# ardu_uno_car.net
KiCad netlist of a schematic drawn in EAGLE
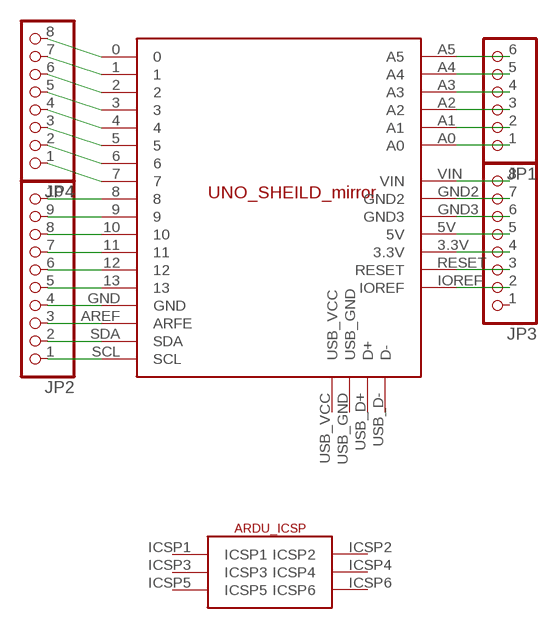
[diagram p0: schematic, sheet 1]

(export (version "E")
  (design (tool "Eeschema 10.0.6"))
  (components
    (comp (ref "JP1")
      (value "PINHEAD_PINHD-1X6")
      (footprint "eagle-import:PINHEAD_1X06")
      (libsource (lib "eagle-import") (part "PINHEAD_PINHD-1X6"))
    )
    (comp (ref "JP2")
      (value "PINHD-1X10")
      (footprint "eagle-import:1X10")
      (libsource (lib "eagle-import") (part "PINHD-1X10"))
    )
    (comp (ref "JP3")
      (value "PINHEAD_PINHD-1X8")
      (footprint "eagle-import:PINHEAD_1X08")
      (libsource (lib "eagle-import") (part "PINHEAD_PINHD-1X8"))
    )
    (comp (ref "JP4")
      (value "PINHEAD_PINHD-1X8")
      (footprint "eagle-import:PINHEAD_1X08")
      (libsource (lib "eagle-import") (part "PINHEAD_PINHD-1X8"))
    )
    (comp (ref "U$1")
      (value "UNO_SHEILD_MIRROR_CH_VER")
      (footprint "eagle-import:UNO_SHEILD_MIRROR_CH_VER")
      (libsource (lib "eagle-import") (part "UNO_SHEILD_MIRROR_CH_VER"))
    )
  )
  (nets
    (net (code "1") (name "Net-(JP1-Pad1)") (class "Default")
      (node (ref "JP1") (pin "1") (pinfunction "1_1") (pintype "passive"))
      (node (ref "U$1") (pin "A0") (pinfunction "A0_A0") (pintype "bidirectional"))
    )
    (net (code "2") (name "Net-(JP1-Pad2)") (class "Default")
      (node (ref "JP1") (pin "2") (pinfunction "2_2") (pintype "passive"))
      (node (ref "U$1") (pin "A1") (pinfunction "A1_A1") (pintype "bidirectional"))
    )
    (net (code "3") (name "Net-(JP1-Pad3)") (class "Default")
      (node (ref "JP1") (pin "3") (pinfunction "3_3") (pintype "passive"))
      (node (ref "U$1") (pin "A2") (pinfunction "A2_A2") (pintype "bidirectional"))
    )
    (net (code "4") (name "Net-(JP1-Pad4)") (class "Default")
      (node (ref "JP1") (pin "4") (pinfunction "4_4") (pintype "passive"))
      (node (ref "U$1") (pin "A3") (pinfunction "A3_A3") (pintype "bidirectional"))
    )
    (net (code "5") (name "Net-(JP1-Pad5)") (class "Default")
      (node (ref "JP1") (pin "5") (pinfunction "5_5") (pintype "passive"))
      (node (ref "U$1") (pin "A4") (pinfunction "A4_A4") (pintype "bidirectional"))
    )
    (net (code "6") (name "Net-(JP1-Pad6)") (class "Default")
      (node (ref "JP1") (pin "6") (pinfunction "6_6") (pintype "passive"))
      (node (ref "U$1") (pin "A5") (pinfunction "A5_A5") (pintype "bidirectional"))
    )
    (net (code "7") (name "Net-(JP2-Pad1)") (class "Default")
      (node (ref "JP2") (pin "1") (pinfunction "1_1") (pintype "passive"))
      (node (ref "U$1") (pin "SCL") (pinfunction "SCL_SCL") (pintype "bidirectional"))
    )
    (net (code "8") (name "Net-(JP2-Pad2)") (class "Default")
      (node (ref "JP2") (pin "2") (pinfunction "2_2") (pintype "passive"))
      (node (ref "U$1") (pin "SDA") (pinfunction "SDA_SDA") (pintype "bidirectional"))
    )
    (net (code "9") (name "Net-(JP2-Pad4)") (class "Default")
      (node (ref "JP2") (pin "4") (pinfunction "4_4") (pintype "passive"))
      (node (ref "U$1") (pin "GND") (pinfunction "GND_GND") (pintype "bidirectional"))
    )
    (net (code "10") (name "Net-(JP2-Pad5)") (class "Default")
      (node (ref "JP2") (pin "5") (pinfunction "5_5") (pintype "passive"))
      (node (ref "U$1") (pin "13") (pinfunction "13_13") (pintype "bidirectional"))
    )
    (net (code "11") (name "Net-(JP2-Pad6)") (class "Default")
      (node (ref "JP2") (pin "6") (pinfunction "6_6") (pintype "passive"))
      (node (ref "U$1") (pin "12") (pinfunction "12_12") (pintype "bidirectional"))
    )
    (net (code "12") (name "Net-(JP2-Pad7)") (class "Default")
      (node (ref "JP2") (pin "7") (pinfunction "7_7") (pintype "passive"))
      (node (ref "U$1") (pin "11") (pinfunction "11_11") (pintype "bidirectional"))
    )
    (net (code "13") (name "Net-(JP2-Pad8)") (class "Default")
      (node (ref "JP2") (pin "8") (pinfunction "8_8") (pintype "passive"))
      (node (ref "U$1") (pin "10") (pinfunction "10_10") (pintype "bidirectional"))
    )
    (net (code "14") (name "Net-(JP2-Pad9)") (class "Default")
      (node (ref "JP2") (pin "9") (pinfunction "9_9") (pintype "passive"))
      (node (ref "U$1") (pin "9") (pinfunction "9_9") (pintype "bidirectional"))
    )
    (net (code "15") (name "Net-(JP2-Pad10)") (class "Default")
      (node (ref "JP2") (pin "10") (pinfunction "10_10") (pintype "passive"))
      (node (ref "U$1") (pin "8") (pinfunction "8_8") (pintype "bidirectional"))
    )
    (net (code "16") (name "Net-(JP3-Pad2)") (class "Default")
      (node (ref "JP3") (pin "2") (pinfunction "2_2") (pintype "passive"))
      (node (ref "U$1") (pin "IOREF") (pinfunction "IOREF_IOREF") (pintype "bidirectional"))
    )
    (net (code "17") (name "Net-(JP3-Pad3)") (class "Default")
      (node (ref "JP3") (pin "3") (pinfunction "3_3") (pintype "passive"))
      (node (ref "U$1") (pin "RESET") (pinfunction "RESET_RESET") (pintype "bidirectional"))
    )
    (net (code "18") (name "Net-(JP3-Pad4)") (class "Default")
      (node (ref "JP3") (pin "4") (pinfunction "4_4") (pintype "passive"))
      (node (ref "U$1") (pin "3.3V") (pinfunction "3.3V_3.3V") (pintype "bidirectional"))
    )
    (net (code "19") (name "Net-(JP3-Pad5)") (class "Default")
      (node (ref "JP3") (pin "5") (pinfunction "5_5") (pintype "passive"))
      (node (ref "U$1") (pin "5V") (pinfunction "5V_5V") (pintype "bidirectional"))
    )
    (net (code "20") (name "Net-(JP3-Pad6)") (class "Default")
      (node (ref "JP3") (pin "6") (pinfunction "6_6") (pintype "passive"))
      (node (ref "U$1") (pin "GND3") (pinfunction "GND3_GND3") (pintype "bidirectional"))
    )
    (net (code "21") (name "Net-(JP3-Pad7)") (class "Default")
      (node (ref "JP3") (pin "7") (pinfunction "7_7") (pintype "passive"))
      (node (ref "U$1") (pin "GND2") (pinfunction "GND2_GND2") (pintype "bidirectional"))
    )
    (net (code "22") (name "Net-(JP3-Pad8)") (class "Default")
      (node (ref "JP3") (pin "8") (pinfunction "8_8") (pintype "passive"))
      (node (ref "U$1") (pin "VIN") (pinfunction "VIN_VIN") (pintype "bidirectional"))
    )
    (net (code "23") (name "Net-(JP4-Pad1)") (class "Default")
      (node (ref "JP4") (pin "1") (pinfunction "1_1") (pintype "passive"))
      (node (ref "U$1") (pin "7") (pinfunction "7_7") (pintype "bidirectional"))
    )
    (net (code "24") (name "Net-(JP4-Pad2)") (class "Default")
      (node (ref "JP4") (pin "2") (pinfunction "2_2") (pintype "passive"))
      (node (ref "U$1") (pin "6") (pinfunction "6_6") (pintype "bidirectional"))
    )
    (net (code "25") (name "Net-(JP4-Pad3)") (class "Default")
      (node (ref "JP4") (pin "3") (pinfunction "3_3") (pintype "passive"))
      (node (ref "U$1") (pin "5") (pinfunction "5_5") (pintype "bidirectional"))
    )
    (net (code "26") (name "Net-(JP4-Pad4)") (class "Default")
      (node (ref "JP4") (pin "4") (pinfunction "4_4") (pintype "passive"))
      (node (ref "U$1") (pin "4") (pinfunction "4_4") (pintype "bidirectional"))
    )
    (net (code "27") (name "Net-(JP4-Pad5)") (class "Default")
      (node (ref "JP4") (pin "5") (pinfunction "5_5") (pintype "passive"))
      (node (ref "U$1") (pin "3") (pinfunction "3_3") (pintype "bidirectional"))
    )
    (net (code "28") (name "Net-(JP4-Pad6)") (class "Default")
      (node (ref "JP4") (pin "6") (pinfunction "6_6") (pintype "passive"))
      (node (ref "U$1") (pin "2") (pinfunction "2_2") (pintype "bidirectional"))
    )
    (net (code "29") (name "Net-(JP4-Pad7)") (class "Default")
      (node (ref "JP4") (pin "7") (pinfunction "7_7") (pintype "passive"))
      (node (ref "U$1") (pin "1") (pinfunction "1_1") (pintype "bidirectional"))
    )
    (net (code "30") (name "Net-(JP4-Pad8)") (class "Default")
      (node (ref "JP4") (pin "8") (pinfunction "8_8") (pintype "passive"))
      (node (ref "U$1") (pin "0") (pinfunction "0_0") (pintype "bidirectional"))
    )
    (net (code "31") (name "Net-(U$1-ARFE)") (class "Default")
      (node (ref "JP2") (pin "3") (pinfunction "3_3") (pintype "passive"))
      (node (ref "U$1") (pin "AREF") (pinfunction "ARFE_AREF") (pintype "bidirectional"))
    )
    (net (code "32") (name "unconnected-(JP3-Pad1)") (class "Default")
      (node (ref "JP3") (pin "1") (pinfunction "1_1") (pintype "passive"))
    )
    (net (code "33") (name "unconnected-(U$1-D+-PadUSB_D+)") (class "Default")
      (node (ref "U$1") (pin "USB_D+") (pinfunction "D+_USB_D+") (pintype "bidirectional"))
    )
    (net (code "34") (name "unconnected-(U$1-D--PadUSB_D-)") (class "Default")
      (node (ref "U$1") (pin "USB_D-") (pinfunction "D-_USB_D-") (pintype "bidirectional"))
    )
    (net (code "35") (name "unconnected-(U$1-PadICSP1)") (class "Default")
      (node (ref "U$1") (pin "ICSP1") (pinfunction "ICSP1_ICSP1") (pintype "bidirectional"))
    )
    (net (code "36") (name "unconnected-(U$1-PadICSP2)") (class "Default")
      (node (ref "U$1") (pin "ICSP2") (pinfunction "ICSP2_ICSP2") (pintype "bidirectional"))
    )
    (net (code "37") (name "unconnected-(U$1-PadICSP3)") (class "Default")
      (node (ref "U$1") (pin "ICSP3") (pinfunction "ICSP3_ICSP3") (pintype "bidirectional"))
    )
    (net (code "38") (name "unconnected-(U$1-PadICSP4)") (class "Default")
      (node (ref "U$1") (pin "ICSP4") (pinfunction "ICSP4_ICSP4") (pintype "bidirectional"))
    )
    (net (code "39") (name "unconnected-(U$1-PadICSP5)") (class "Default")
      (node (ref "U$1") (pin "ICSP5") (pinfunction "ICSP5_ICSP5") (pintype "bidirectional"))
    )
    (net (code "40") (name "unconnected-(U$1-PadICSP6)") (class "Default")
      (node (ref "U$1") (pin "ICSP6") (pinfunction "ICSP6_ICSP6") (pintype "bidirectional"))
    )
    (net (code "41") (name "unconnected-(U$1-PadUSB_GND)") (class "Default")
      (node (ref "U$1") (pin "USB_GND") (pinfunction "USB_GND_USB_GND") (pintype "bidirectional"))
    )
    (net (code "42") (name "unconnected-(U$1-PadUSB_VCC)") (class "Default")
      (node (ref "U$1") (pin "USB_VCC") (pinfunction "USB_VCC_USB_VCC") (pintype "bidirectional"))
    )
  )
)
